# Rover_Motor_hat.net
KiCad netlist of a schematic drawn in Altium Designer
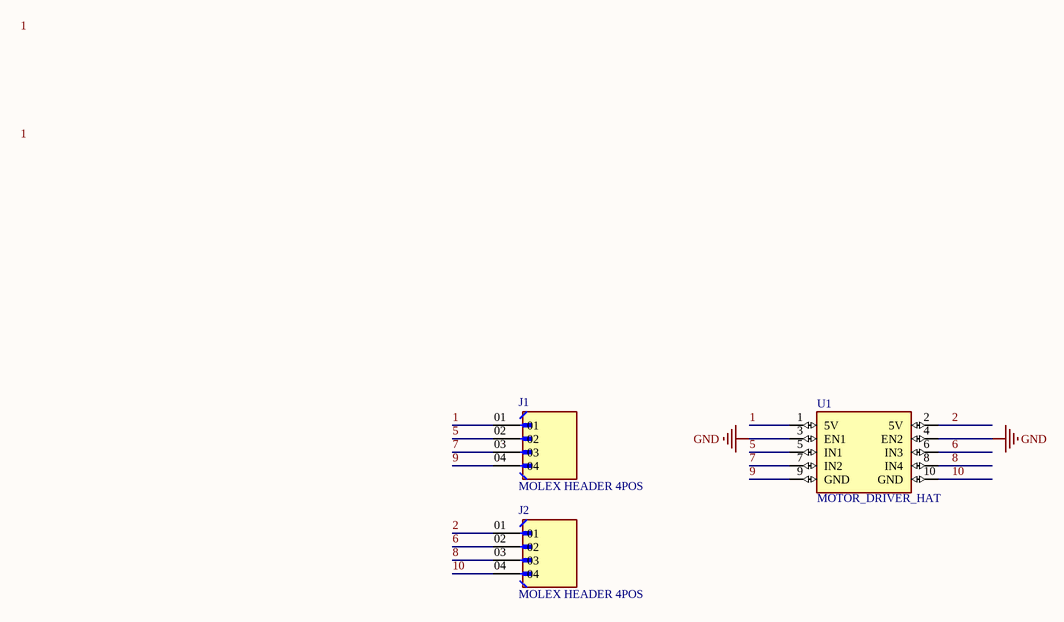
[diagram p0: Rover_Motor_hat.SchDoc]

(export (version "E")
  (design (tool "Eeschema 10.0.6"))
  (components
    (comp (ref "J1")
      (value "MOLEX HEADER 4POS")
      (footprint "MOLEX_35362-0450")
      (description "Connector Header Through Hole 4 position 0.079 (2.00mm)")
      (fields (field (name "MP") "35362-0450") (field (name "MF") "Molex"))
      (libsource (lib "35362-0450") (part "35362-0450"))
    )
    (comp (ref "J2")
      (value "MOLEX HEADER 4POS")
      (footprint "MOLEX_35362-0450")
      (description "Connector Header Through Hole 4 position 0.079 (2.00mm)")
      (fields (field (name "MP") "35362-0450") (field (name "MF") "Molex"))
      (libsource (lib "35362-0450") (part "35362-0450"))
    )
    (comp (ref "U1")
      (value "MOTOR_DRIVER_HAT")
      (footprint "MOTOR_DRIVER_HAT")
      (libsource (lib "Schlib2") (part "MOTOR_DRIVER_HAT"))
    )
  )
  (nets
    (net (code "1") (name "/1") (class "Default")
      (node (ref "J1") (pin "01") (pinfunction "01_01") (pintype "passive"))
      (node (ref "U1") (pin "1") (pinfunction "5V_1") (pintype "bidirectional"))
    )
    (net (code "2") (name "/2") (class "Default")
      (node (ref "J2") (pin "01") (pinfunction "01_01") (pintype "passive"))
      (node (ref "U1") (pin "2") (pinfunction "5V_2") (pintype "bidirectional"))
    )
    (net (code "3") (name "/5") (class "Default")
      (node (ref "J1") (pin "02") (pinfunction "02_02") (pintype "passive"))
      (node (ref "U1") (pin "5") (pinfunction "IN1_5") (pintype "bidirectional"))
    )
    (net (code "4") (name "/6") (class "Default")
      (node (ref "J2") (pin "02") (pinfunction "02_02") (pintype "passive"))
      (node (ref "U1") (pin "6") (pinfunction "IN3_6") (pintype "bidirectional"))
    )
    (net (code "5") (name "/7") (class "Default")
      (node (ref "J1") (pin "03") (pinfunction "03_03") (pintype "passive"))
      (node (ref "U1") (pin "7") (pinfunction "IN2_7") (pintype "bidirectional"))
    )
    (net (code "6") (name "/8") (class "Default")
      (node (ref "J2") (pin "03") (pinfunction "03_03") (pintype "passive"))
      (node (ref "U1") (pin "8") (pinfunction "IN4_8") (pintype "bidirectional"))
    )
    (net (code "7") (name "/9") (class "Default")
      (node (ref "J1") (pin "04") (pinfunction "04_04") (pintype "passive"))
      (node (ref "U1") (pin "9") (pinfunction "GND_9") (pintype "bidirectional"))
    )
    (net (code "8") (name "/10") (class "Default")
      (node (ref "J2") (pin "04") (pinfunction "04_04") (pintype "passive"))
      (node (ref "U1") (pin "10") (pinfunction "GND_10") (pintype "bidirectional"))
    )
    (net (code "9") (name "GND") (class "Default")
      (node (ref "U1") (pin "3") (pinfunction "EN1_3") (pintype "bidirectional"))
      (node (ref "U1") (pin "4") (pinfunction "EN2_4") (pintype "bidirectional"))
    )
  )
)
